# Stromversorgung.net
KiCad netlist of a schematic drawn in EAGLE
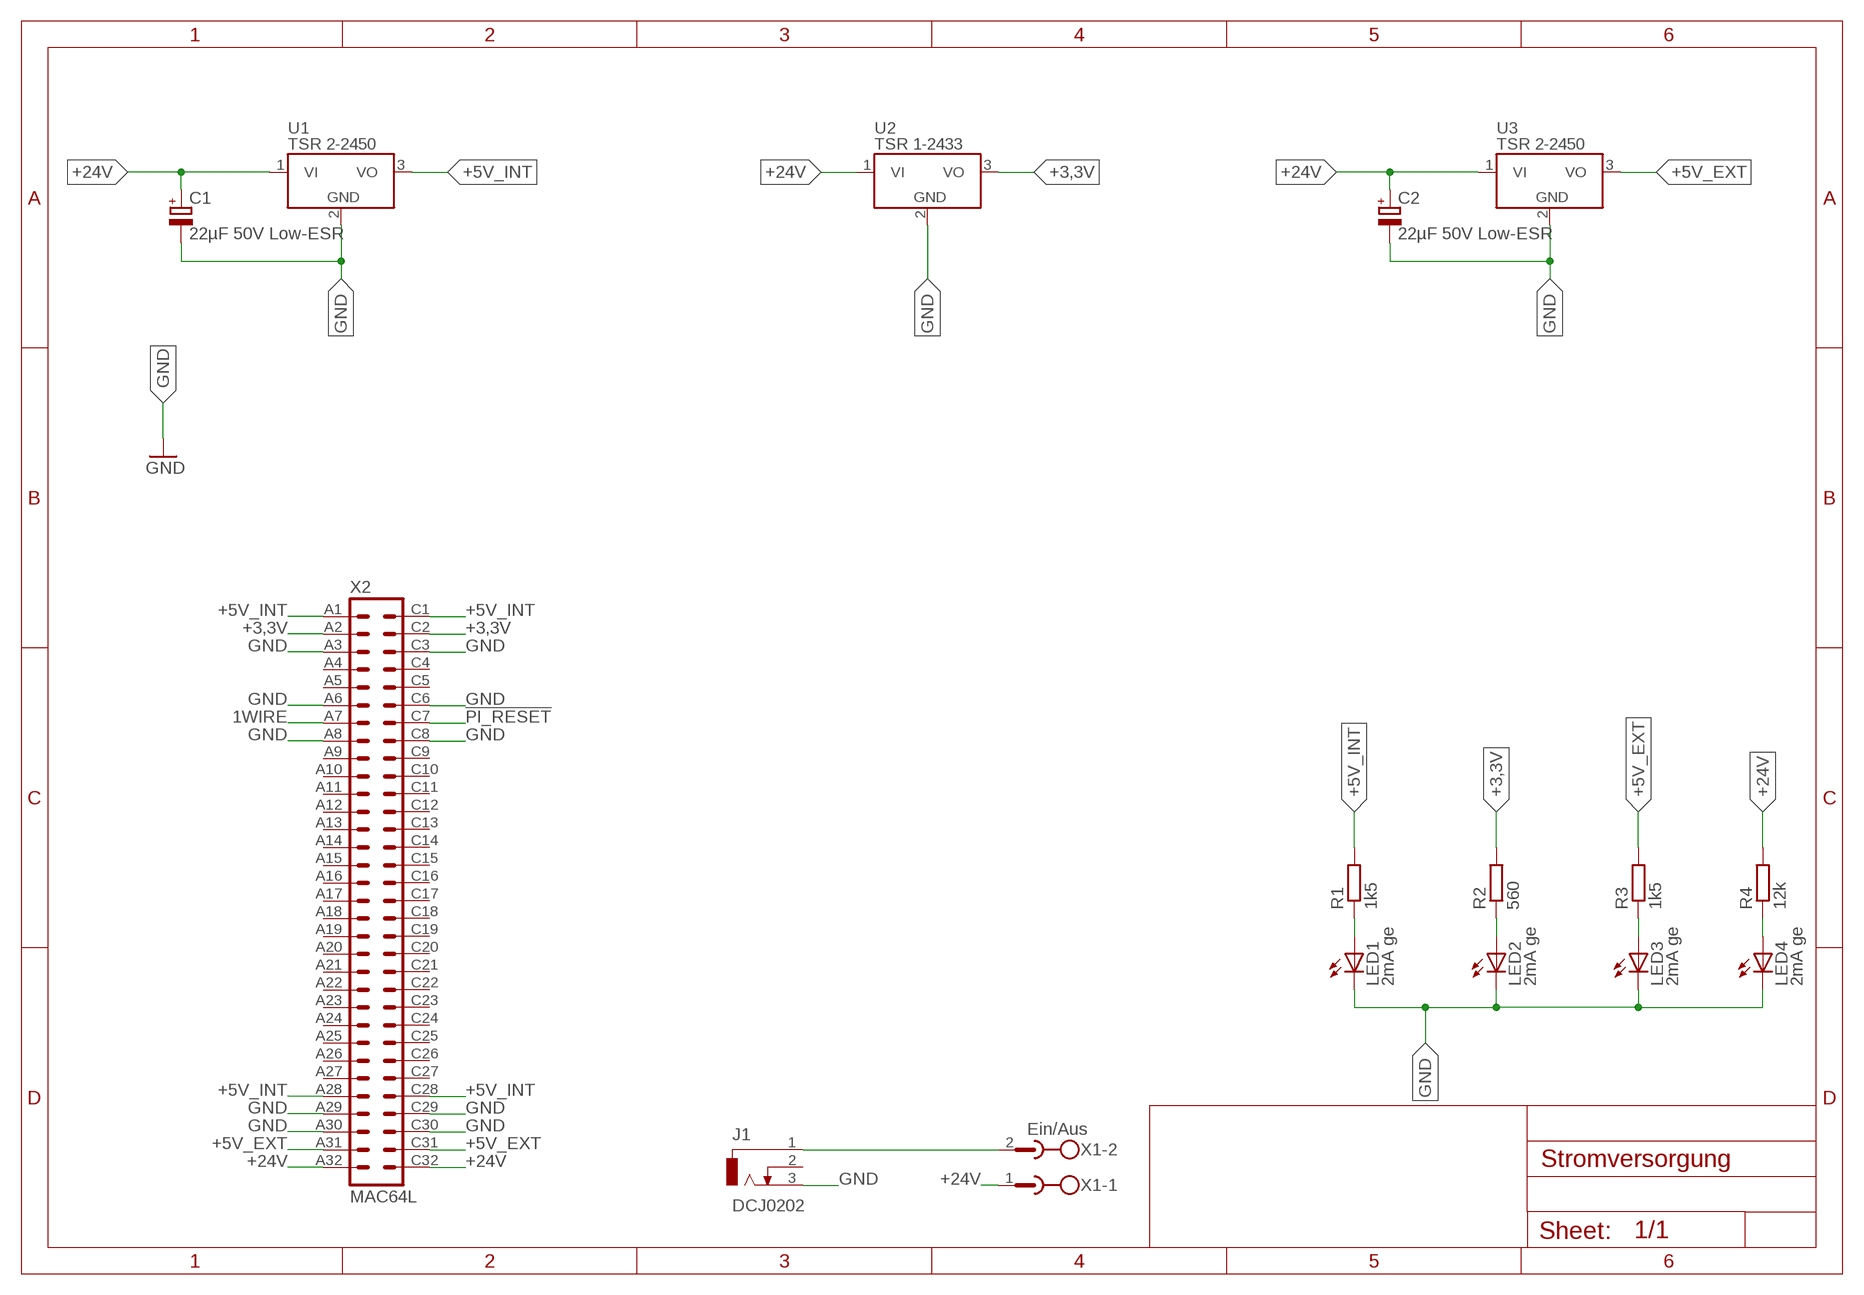
[diagram p0: schematic, sheet 1]

(export (version "E")
  (design (tool "Eeschema 10.0.6"))
  (components
    (comp (ref "C1")
      (value "22µF 50V Low-ESR")
      (footprint "eagle-import:E2-5")
      (libsource (lib "eagle-import") (part "CPOL-EUE2-5"))
    )
    (comp (ref "C2")
      (value "22µF 50V Low-ESR")
      (footprint "eagle-import:E2-5")
      (libsource (lib "eagle-import") (part "CPOL-EUE2-5"))
    )
    (comp (ref "J1")
      (value "DCJ0202")
      (footprint "eagle-import:DCJ0202")
      (libsource (lib "eagle-import") (part "DCJ0202"))
    )
    (comp (ref "LED1")
      (value "2mA ge")
      (footprint "eagle-import:LED3MM")
      (libsource (lib "eagle-import") (part "LED3MM"))
    )
    (comp (ref "LED2")
      (value "2mA ge")
      (footprint "eagle-import:LED3MM")
      (libsource (lib "eagle-import") (part "LED3MM"))
    )
    (comp (ref "LED3")
      (value "2mA ge")
      (footprint "eagle-import:LED3MM")
      (libsource (lib "eagle-import") (part "LED3MM"))
    )
    (comp (ref "LED4")
      (value "2mA ge")
      (footprint "eagle-import:LED3MM")
      (libsource (lib "eagle-import") (part "LED3MM"))
    )
    (comp (ref "R1")
      (value "1k5")
      (footprint "eagle-import:0204_5")
      (libsource (lib "eagle-import") (part "R-EU_0204/5"))
    )
    (comp (ref "R2")
      (value "560")
      (footprint "eagle-import:0204_5")
      (libsource (lib "eagle-import") (part "R-EU_0204/5"))
    )
    (comp (ref "R3")
      (value "1k5")
      (footprint "eagle-import:0204_5")
      (libsource (lib "eagle-import") (part "R-EU_0204/5"))
    )
    (comp (ref "R4")
      (value "12k")
      (footprint "eagle-import:0204_5")
      (libsource (lib "eagle-import") (part "R-EU_0204/5"))
    )
    (comp (ref "U1")
      (value "TSR 2-2450")
      (footprint "eagle-import:TSR-1")
      (libsource (lib "eagle-import") (part "TSR_1-2450"))
    )
    (comp (ref "U2")
      (value "TSR 1-2433")
      (footprint "eagle-import:TSR-1")
      (libsource (lib "eagle-import") (part "TSR_1-2433"))
    )
    (comp (ref "U3")
      (value "TSR 2-2450")
      (footprint "eagle-import:TSR-1")
      (libsource (lib "eagle-import") (part "TSR_1-2450"))
    )
    (comp (ref "X1")
      (value "Ein/Aus")
      (footprint "eagle-import:MSTBV2")
      (fields (field (name "MPN") "MSTBV 2,5/2-GF-5.08"))
      (libsource (lib "eagle-import") (part "MSTBV2"))
    )
    (comp (ref "X2")
      (value "MAC64L")
      (footprint "eagle-import:MAC64L")
      (libsource (lib "eagle-import") (part "MAC64L"))
    )
  )
  (nets
    (net (code "1") (name "+3,3V") (class "Default")
      (node (ref "R2") (pin "2") (pinfunction "2_2") (pintype "passive"))
      (node (ref "U2") (pin "3") (pinfunction "VO_3") (pintype "power_in"))
      (node (ref "X2") (pin "A2") (pinfunction "A2_A2") (pintype "passive"))
      (node (ref "X2") (pin "C2") (pinfunction "C2_C2") (pintype "passive"))
    )
    (net (code "2") (name "+5V_EXT") (class "Default")
      (node (ref "R3") (pin "2") (pinfunction "2_2") (pintype "passive"))
      (node (ref "U3") (pin "3") (pinfunction "VO_3") (pintype "power_in"))
      (node (ref "X2") (pin "A31") (pinfunction "A31_A31") (pintype "passive"))
      (node (ref "X2") (pin "C31") (pinfunction "C31_C31") (pintype "passive"))
    )
    (net (code "3") (name "+5V_INT") (class "Default")
      (node (ref "R1") (pin "2") (pinfunction "2_2") (pintype "passive"))
      (node (ref "U1") (pin "3") (pinfunction "VO_3") (pintype "power_in"))
      (node (ref "X2") (pin "A1") (pinfunction "A1_A1") (pintype "passive"))
      (node (ref "X2") (pin "A28") (pinfunction "A28_A28") (pintype "passive"))
      (node (ref "X2") (pin "C1") (pinfunction "C1_C1") (pintype "passive"))
      (node (ref "X2") (pin "C28") (pinfunction "C28_C28") (pintype "passive"))
    )
    (net (code "4") (name "+24V") (class "Default")
      (node (ref "C1") (pin "+") (pinfunction "+_+") (pintype "passive"))
      (node (ref "C2") (pin "+") (pinfunction "+_+") (pintype "passive"))
      (node (ref "R4") (pin "2") (pinfunction "2_2") (pintype "passive"))
      (node (ref "U1") (pin "1") (pinfunction "VI_1") (pintype "power_in"))
      (node (ref "U2") (pin "1") (pinfunction "VI_1") (pintype "power_in"))
      (node (ref "U3") (pin "1") (pinfunction "VI_1") (pintype "power_in"))
      (node (ref "X1") (pin "1") (pinfunction "1_1") (pintype "passive"))
      (node (ref "X2") (pin "A32") (pinfunction "A32_A32") (pintype "passive"))
      (node (ref "X2") (pin "C32") (pinfunction "C32_C32") (pintype "passive"))
    )
    (net (code "5") (name "/1WIRE") (class "Default")
      (node (ref "X2") (pin "A7") (pinfunction "A7_A7") (pintype "passive"))
    )
    (net (code "6") (name "/~{PI_RESET}") (class "Default")
      (node (ref "X2") (pin "C7") (pinfunction "C7_C7") (pintype "passive"))
    )
    (net (code "7") (name "GND") (class "Default")
      (node (ref "C1") (pin "-") (pinfunction "-_-") (pintype "passive"))
      (node (ref "C2") (pin "-") (pinfunction "-_-") (pintype "passive"))
      (node (ref "J1") (pin "3") (pinfunction "3_3") (pintype "passive"))
      (node (ref "LED1") (pin "K") (pinfunction "C_K") (pintype "passive"))
      (node (ref "LED2") (pin "K") (pinfunction "C_K") (pintype "passive"))
      (node (ref "LED3") (pin "K") (pinfunction "C_K") (pintype "passive"))
      (node (ref "LED4") (pin "K") (pinfunction "C_K") (pintype "passive"))
      (node (ref "U1") (pin "2") (pinfunction "GND_2") (pintype "power_in"))
      (node (ref "U2") (pin "2") (pinfunction "GND_2") (pintype "power_in"))
      (node (ref "U3") (pin "2") (pinfunction "GND_2") (pintype "power_in"))
      (node (ref "X2") (pin "A29") (pinfunction "A29_A29") (pintype "passive"))
      (node (ref "X2") (pin "A3") (pinfunction "A3_A3") (pintype "passive"))
      (node (ref "X2") (pin "A30") (pinfunction "A30_A30") (pintype "passive"))
      (node (ref "X2") (pin "A6") (pinfunction "A6_A6") (pintype "passive"))
      (node (ref "X2") (pin "A8") (pinfunction "A8_A8") (pintype "passive"))
      (node (ref "X2") (pin "C29") (pinfunction "C29_C29") (pintype "passive"))
      (node (ref "X2") (pin "C3") (pinfunction "C3_C3") (pintype "passive"))
      (node (ref "X2") (pin "C30") (pinfunction "C30_C30") (pintype "passive"))
      (node (ref "X2") (pin "C6") (pinfunction "C6_C6") (pintype "passive"))
      (node (ref "X2") (pin "C8") (pinfunction "C8_C8") (pintype "passive"))
    )
    (net (code "8") (name "Net-(LED1-PadA)") (class "Default")
      (node (ref "LED1") (pin "A") (pinfunction "A_A") (pintype "passive"))
      (node (ref "R1") (pin "1") (pinfunction "1_1") (pintype "passive"))
    )
    (net (code "9") (name "Net-(LED2-PadA)") (class "Default")
      (node (ref "LED2") (pin "A") (pinfunction "A_A") (pintype "passive"))
      (node (ref "R2") (pin "1") (pinfunction "1_1") (pintype "passive"))
    )
    (net (code "10") (name "Net-(LED3-PadA)") (class "Default")
      (node (ref "LED3") (pin "A") (pinfunction "A_A") (pintype "passive"))
      (node (ref "R3") (pin "1") (pinfunction "1_1") (pintype "passive"))
    )
    (net (code "11") (name "Net-(LED4-PadA)") (class "Default")
      (node (ref "LED4") (pin "A") (pinfunction "A_A") (pintype "passive"))
      (node (ref "R4") (pin "1") (pinfunction "1_1") (pintype "passive"))
    )
    (net (code "12") (name "Net-(X1B-1)") (class "Default")
      (node (ref "J1") (pin "1") (pinfunction "1_1") (pintype "passive"))
      (node (ref "X1") (pin "2") (pinfunction "1_2") (pintype "passive"))
    )
    (net (code "13") (name "unconnected-(J1-Pad2)") (class "Default")
      (node (ref "J1") (pin "2") (pinfunction "2_2") (pintype "passive"))
    )
    (net (code "14") (name "unconnected-(X2-PadA4)") (class "Default")
      (node (ref "X2") (pin "A4") (pinfunction "A4_A4") (pintype "passive"))
    )
    (net (code "15") (name "unconnected-(X2-PadA5)") (class "Default")
      (node (ref "X2") (pin "A5") (pinfunction "A5_A5") (pintype "passive"))
    )
    (net (code "16") (name "unconnected-(X2-PadA9)") (class "Default")
      (node (ref "X2") (pin "A9") (pinfunction "A9_A9") (pintype "passive"))
    )
    (net (code "17") (name "unconnected-(X2-PadA10)") (class "Default")
      (node (ref "X2") (pin "A10") (pinfunction "A10_A10") (pintype "passive"))
    )
    (net (code "18") (name "unconnected-(X2-PadA11)") (class "Default")
      (node (ref "X2") (pin "A11") (pinfunction "A11_A11") (pintype "passive"))
    )
    (net (code "19") (name "unconnected-(X2-PadA12)") (class "Default")
      (node (ref "X2") (pin "A12") (pinfunction "A12_A12") (pintype "passive"))
    )
    (net (code "20") (name "unconnected-(X2-PadA13)") (class "Default")
      (node (ref "X2") (pin "A13") (pinfunction "A13_A13") (pintype "passive"))
    )
    (net (code "21") (name "unconnected-(X2-PadA14)") (class "Default")
      (node (ref "X2") (pin "A14") (pinfunction "A14_A14") (pintype "passive"))
    )
    (net (code "22") (name "unconnected-(X2-PadA15)") (class "Default")
      (node (ref "X2") (pin "A15") (pinfunction "A15_A15") (pintype "passive"))
    )
    (net (code "23") (name "unconnected-(X2-PadA16)") (class "Default")
      (node (ref "X2") (pin "A16") (pinfunction "A16_A16") (pintype "passive"))
    )
    (net (code "24") (name "unconnected-(X2-PadA17)") (class "Default")
      (node (ref "X2") (pin "A17") (pinfunction "A17_A17") (pintype "passive"))
    )
    (net (code "25") (name "unconnected-(X2-PadA18)") (class "Default")
      (node (ref "X2") (pin "A18") (pinfunction "A18_A18") (pintype "passive"))
    )
    (net (code "26") (name "unconnected-(X2-PadA19)") (class "Default")
      (node (ref "X2") (pin "A19") (pinfunction "A19_A19") (pintype "passive"))
    )
    (net (code "27") (name "unconnected-(X2-PadA20)") (class "Default")
      (node (ref "X2") (pin "A20") (pinfunction "A20_A20") (pintype "passive"))
    )
    (net (code "28") (name "unconnected-(X2-PadA21)") (class "Default")
      (node (ref "X2") (pin "A21") (pinfunction "A21_A21") (pintype "passive"))
    )
    (net (code "29") (name "unconnected-(X2-PadA22)") (class "Default")
      (node (ref "X2") (pin "A22") (pinfunction "A22_A22") (pintype "passive"))
    )
    (net (code "30") (name "unconnected-(X2-PadA23)") (class "Default")
      (node (ref "X2") (pin "A23") (pinfunction "A23_A23") (pintype "passive"))
    )
    (net (code "31") (name "unconnected-(X2-PadA24)") (class "Default")
      (node (ref "X2") (pin "A24") (pinfunction "A24_A24") (pintype "passive"))
    )
    (net (code "32") (name "unconnected-(X2-PadA25)") (class "Default")
      (node (ref "X2") (pin "A25") (pinfunction "A25_A25") (pintype "passive"))
    )
    (net (code "33") (name "unconnected-(X2-PadA26)") (class "Default")
      (node (ref "X2") (pin "A26") (pinfunction "A26_A26") (pintype "passive"))
    )
    (net (code "34") (name "unconnected-(X2-PadA27)") (class "Default")
      (node (ref "X2") (pin "A27") (pinfunction "A27_A27") (pintype "passive"))
    )
    (net (code "35") (name "unconnected-(X2-PadC4)") (class "Default")
      (node (ref "X2") (pin "C4") (pinfunction "C4_C4") (pintype "passive"))
    )
    (net (code "36") (name "unconnected-(X2-PadC5)") (class "Default")
      (node (ref "X2") (pin "C5") (pinfunction "C5_C5") (pintype "passive"))
    )
    (net (code "37") (name "unconnected-(X2-PadC9)") (class "Default")
      (node (ref "X2") (pin "C9") (pinfunction "C9_C9") (pintype "passive"))
    )
    (net (code "38") (name "unconnected-(X2-PadC10)") (class "Default")
      (node (ref "X2") (pin "C10") (pinfunction "C10_C10") (pintype "passive"))
    )
    (net (code "39") (name "unconnected-(X2-PadC11)") (class "Default")
      (node (ref "X2") (pin "C11") (pinfunction "C11_C11") (pintype "passive"))
    )
    (net (code "40") (name "unconnected-(X2-PadC12)") (class "Default")
      (node (ref "X2") (pin "C12") (pinfunction "C12_C12") (pintype "passive"))
    )
    (net (code "41") (name "unconnected-(X2-PadC13)") (class "Default")
      (node (ref "X2") (pin "C13") (pinfunction "C13_C13") (pintype "passive"))
    )
    (net (code "42") (name "unconnected-(X2-PadC14)") (class "Default")
      (node (ref "X2") (pin "C14") (pinfunction "C14_C14") (pintype "passive"))
    )
    (net (code "43") (name "unconnected-(X2-PadC15)") (class "Default")
      (node (ref "X2") (pin "C15") (pinfunction "C15_C15") (pintype "passive"))
    )
    (net (code "44") (name "unconnected-(X2-PadC16)") (class "Default")
      (node (ref "X2") (pin "C16") (pinfunction "C16_C16") (pintype "passive"))
    )
    (net (code "45") (name "unconnected-(X2-PadC17)") (class "Default")
      (node (ref "X2") (pin "C17") (pinfunction "C17_C17") (pintype "passive"))
    )
    (net (code "46") (name "unconnected-(X2-PadC18)") (class "Default")
      (node (ref "X2") (pin "C18") (pinfunction "C18_C18") (pintype "passive"))
    )
    (net (code "47") (name "unconnected-(X2-PadC19)") (class "Default")
      (node (ref "X2") (pin "C19") (pinfunction "C19_C19") (pintype "passive"))
    )
    (net (code "48") (name "unconnected-(X2-PadC20)") (class "Default")
      (node (ref "X2") (pin "C20") (pinfunction "C20_C20") (pintype "passive"))
    )
    (net (code "49") (name "unconnected-(X2-PadC21)") (class "Default")
      (node (ref "X2") (pin "C21") (pinfunction "C21_C21") (pintype "passive"))
    )
    (net (code "50") (name "unconnected-(X2-PadC22)") (class "Default")
      (node (ref "X2") (pin "C22") (pinfunction "C22_C22") (pintype "passive"))
    )
    (net (code "51") (name "unconnected-(X2-PadC23)") (class "Default")
      (node (ref "X2") (pin "C23") (pinfunction "C23_C23") (pintype "passive"))
    )
    (net (code "52") (name "unconnected-(X2-PadC24)") (class "Default")
      (node (ref "X2") (pin "C24") (pinfunction "C24_C24") (pintype "passive"))
    )
    (net (code "53") (name "unconnected-(X2-PadC25)") (class "Default")
      (node (ref "X2") (pin "C25") (pinfunction "C25_C25") (pintype "passive"))
    )
    (net (code "54") (name "unconnected-(X2-PadC26)") (class "Default")
      (node (ref "X2") (pin "C26") (pinfunction "C26_C26") (pintype "passive"))
    )
    (net (code "55") (name "unconnected-(X2-PadC27)") (class "Default")
      (node (ref "X2") (pin "C27") (pinfunction "C27_C27") (pintype "passive"))
    )
  )
)
